# comms_v2.net
KiCad netlist of a schematic drawn in EAGLE
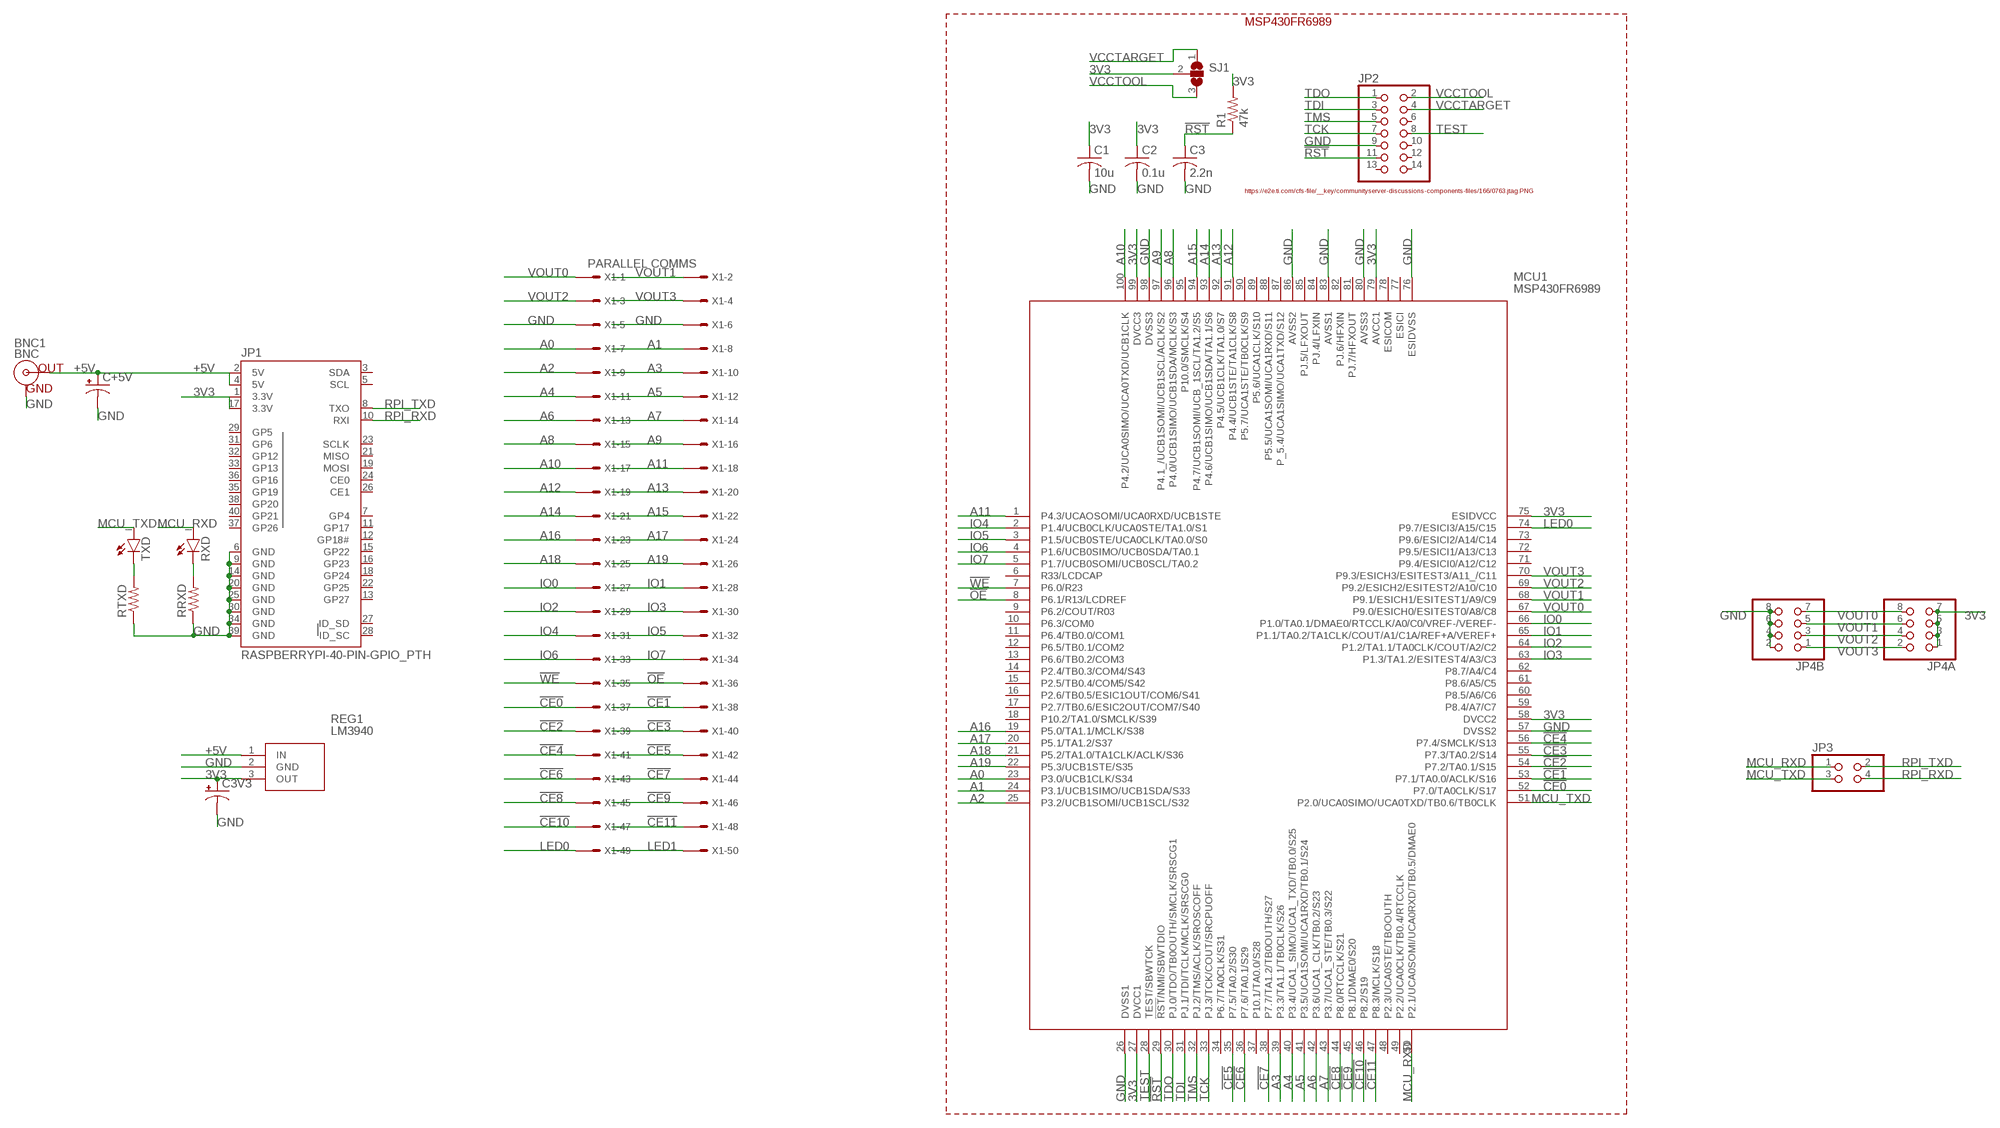
[diagram p0: schematic, sheet 1]

(export (version "E")
  (design (tool "Eeschema 10.0.6"))
  (components
    (comp (ref "BNC1")
      (value "BNC")
      (footprint "eagle-import:BNC")
      (libsource (lib "eagle-import") (part "BNCPTH"))
    )
    (comp (ref "C+5V")
      (value "CPOL-USE2.5-6")
      (footprint "eagle-import:E2,5-6")
      (libsource (lib "eagle-import") (part "CPOL-USE2.5-6"))
    )
    (comp (ref "C1")
      (value "10u")
      (footprint "eagle-import:C0805")
      (libsource (lib "eagle-import") (part "C-USC0805"))
    )
    (comp (ref "C2")
      (value "0.1u")
      (footprint "eagle-import:C0805")
      (libsource (lib "eagle-import") (part "C-USC0805"))
    )
    (comp (ref "C3")
      (value "2.2n")
      (footprint "eagle-import:C0805")
      (libsource (lib "eagle-import") (part "C-USC0805"))
    )
    (comp (ref "C3V3")
      (value "CPOL-USE2.5-6")
      (footprint "eagle-import:E2,5-6")
      (libsource (lib "eagle-import") (part "CPOL-USE2.5-6"))
    )
    (comp (ref "JP1")
      (value "RASPBERRYPI-40-PIN-GPIO_PTH")
      (footprint "eagle-import:2X20_SHROUDED")
      (libsource (lib "eagle-import") (part "RASPBERRYPI-40-PIN-GPIO_PTH"))
    )
    (comp (ref "JP2")
      (value "PINHD-2X7")
      (footprint "eagle-import:2X07")
      (libsource (lib "eagle-import") (part "PINHD-2X7"))
    )
    (comp (ref "JP3")
      (value "PINHD-2X2")
      (footprint "eagle-import:2X02")
      (libsource (lib "eagle-import") (part "PINHD-2X2"))
    )
    (comp (ref "JP4A")
      (value "PINHD-2X4")
      (footprint "eagle-import:2X04")
      (libsource (lib "eagle-import") (part "PINHD-2X4"))
    )
    (comp (ref "JP4B")
      (value "PINHD-2X4")
      (footprint "eagle-import:2X04")
      (libsource (lib "eagle-import") (part "PINHD-2X4"))
    )
    (comp (ref "MCU1")
      (value "MSP430FR6989")
      (footprint "eagle-import:QFP50P1600X1600X160-100N")
      (fields
        (field (name "ARROW_PART_NUMBER") "MSP430FR6989IPZR")
        (field (name "MOUSER_PART_NUMBER") "595-MSP430FR6989IPZR")
      )
      (libsource (lib "eagle-import") (part "MSP430FR6989IPZR"))
    )
    (comp (ref "R1")
      (value "47k")
      (footprint "eagle-import:R0805")
      (libsource (lib "eagle-import") (part "R-US_R0805"))
    )
    (comp (ref "REG1")
      (value "LM3940")
      (footprint "eagle-import:TO254P470X1028X1955-3P")
      (fields
        (field (name "ARROW_PART_NUMBER") "LM3940IT-3.3/NOPB")
        (field (name "MOUSER_PART_NUMBER") "926-LM3940IT-3.3NOPB")
      )
      (libsource (lib "eagle-import") (part "LM3940IT-3.3_NOPB"))
    )
    (comp (ref "RRXD")
      (value "R-US_0204/7")
      (footprint "eagle-import:0204_7")
      (libsource (lib "eagle-import") (part "R-US_0204/7"))
    )
    (comp (ref "RTXD")
      (value "R-US_0204/7")
      (footprint "eagle-import:0204_7")
      (libsource (lib "eagle-import") (part "R-US_0204/7"))
    )
    (comp (ref "RXD")
      (value "LED3MM")
      (footprint "eagle-import:LED3MM")
      (libsource (lib "eagle-import") (part "LED3MM"))
    )
    (comp (ref "SJ1")
      (value "SJ2W")
      (footprint "eagle-import:SJ_2")
      (libsource (lib "eagle-import") (part "SJ2W"))
    )
    (comp (ref "TXD")
      (value "LED3MM")
      (footprint "eagle-import:LED3MM")
      (libsource (lib "eagle-import") (part "LED3MM"))
    )
    (comp (ref "X1")
      (value "PARALLEL COMMS")
      (footprint "eagle-import:057-050-1")
      (libsource (lib "eagle-import") (part "057-050-1"))
    )
  )
  (nets
    (net (code "1") (name "/+5V") (class "Default")
      (node (ref "BNC1") (pin "S") (pinfunction "OUT_S") (pintype "bidirectional"))
      (node (ref "C+5V") (pin "+") (pinfunction "+_+") (pintype "passive"))
      (node (ref "JP1") (pin "2") (pinfunction "5V_2") (pintype "power_in"))
      (node (ref "JP1") (pin "4") (pinfunction "5V_4") (pintype "power_in"))
      (node (ref "REG1") (pin "1") (pinfunction "IN_1") (pintype "bidirectional"))
    )
    (net (code "2") (name "/3V3") (class "Default")
      (node (ref "C1") (pin "1") (pinfunction "1_1") (pintype "passive"))
      (node (ref "C2") (pin "1") (pinfunction "1_1") (pintype "passive"))
      (node (ref "C3V3") (pin "+") (pinfunction "+_+") (pintype "passive"))
      (node (ref "JP1") (pin "1") (pinfunction "3.3V_1") (pintype "power_in"))
      (node (ref "JP1") (pin "17") (pinfunction "3.3V_17") (pintype "power_in"))
      (node (ref "JP4A") (pin "1") (pinfunction "1_1") (pintype "passive"))
      (node (ref "JP4A") (pin "3") (pinfunction "3_3") (pintype "passive"))
      (node (ref "JP4A") (pin "5") (pinfunction "5_5") (pintype "passive"))
      (node (ref "JP4A") (pin "7") (pinfunction "7_7") (pintype "passive"))
      (node (ref "MCU1") (pin "27") (pinfunction "DVCC1_27") (pintype "bidirectional"))
      (node (ref "MCU1") (pin "58") (pinfunction "DVCC2_58") (pintype "bidirectional"))
      (node (ref "MCU1") (pin "75") (pinfunction "ESIDVCC_75") (pintype "bidirectional"))
      (node (ref "MCU1") (pin "79") (pinfunction "AVCC1_79") (pintype "bidirectional"))
      (node (ref "MCU1") (pin "99") (pinfunction "DVCC3_99") (pintype "bidirectional"))
      (node (ref "R1") (pin "2") (pinfunction "2_2") (pintype "passive"))
      (node (ref "REG1") (pin "3") (pinfunction "OUT_3") (pintype "bidirectional"))
      (node (ref "SJ1") (pin "2") (pinfunction "2_2") (pintype "passive"))
    )
    (net (code "3") (name "/A0") (class "Default")
      (node (ref "MCU1") (pin "23") (pinfunction "P3.0/UCB1CLK/S34_23") (pintype "bidirectional"))
      (node (ref "X1") (pin "7") (pinfunction "S_7") (pintype "passive"))
    )
    (net (code "4") (name "/A1") (class "Default")
      (node (ref "MCU1") (pin "24") (pinfunction "P3.1/UCB1SIMO/UCB1SDA/S33_24") (pintype "bidirectional"))
      (node (ref "X1") (pin "8") (pinfunction "S_8") (pintype "passive"))
    )
    (net (code "5") (name "/A2") (class "Default")
      (node (ref "MCU1") (pin "25") (pinfunction "P3.2/UCB1SOMI/UCB1SCL/S32_25") (pintype "bidirectional"))
      (node (ref "X1") (pin "9") (pinfunction "S_9") (pintype "passive"))
    )
    (net (code "6") (name "/A3") (class "Default")
      (node (ref "MCU1") (pin "39") (pinfunction "P3.3/TA1.1/TB0CLK/S26_39") (pintype "bidirectional"))
      (node (ref "X1") (pin "10") (pinfunction "S_10") (pintype "passive"))
    )
    (net (code "7") (name "/A4") (class "Default")
      (node (ref "MCU1") (pin "40") (pinfunction "P3.4/UCA1_SIMO/UCA1_TXD/TB0.0/S25_40") (pintype "bidirectional"))
      (node (ref "X1") (pin "11") (pinfunction "S_11") (pintype "passive"))
    )
    (net (code "8") (name "/A5") (class "Default")
      (node (ref "MCU1") (pin "41") (pinfunction "P3.5/UCA1SOMI/UCA1RXD/TB0.1/S24_41") (pintype "bidirectional"))
      (node (ref "X1") (pin "12") (pinfunction "S_12") (pintype "passive"))
    )
    (net (code "9") (name "/A6") (class "Default")
      (node (ref "MCU1") (pin "42") (pinfunction "P3.6/UCA1_CLK/TB0.2/S23_42") (pintype "bidirectional"))
      (node (ref "X1") (pin "13") (pinfunction "S_13") (pintype "passive"))
    )
    (net (code "10") (name "/A7") (class "Default")
      (node (ref "MCU1") (pin "43") (pinfunction "P3.7/UCA1_STE/TB0.3/S22_43") (pintype "bidirectional"))
      (node (ref "X1") (pin "14") (pinfunction "S_14") (pintype "passive"))
    )
    (net (code "11") (name "/A8") (class "Default")
      (node (ref "MCU1") (pin "96") (pinfunction "P4.0/UCB1SIMO/UCB1SDA/MCLK/S3_96") (pintype "bidirectional"))
      (node (ref "X1") (pin "15") (pinfunction "S_15") (pintype "passive"))
    )
    (net (code "12") (name "/A9") (class "Default")
      (node (ref "MCU1") (pin "97") (pinfunction "P4.1_/UCB1SOMI/UCB1SCL/ACLK/S2_97") (pintype "bidirectional"))
      (node (ref "X1") (pin "16") (pinfunction "S_16") (pintype "passive"))
    )
    (net (code "13") (name "/A10") (class "Default")
      (node (ref "MCU1") (pin "100") (pinfunction "P4.2/UCA0SIMO/UCA0TXD/UCB1CLK_100") (pintype "bidirectional"))
      (node (ref "X1") (pin "17") (pinfunction "S_17") (pintype "passive"))
    )
    (net (code "14") (name "/A11") (class "Default")
      (node (ref "MCU1") (pin "1") (pinfunction "P4.3/UCAOSOMI/UCA0RXD/UCB1STE_1") (pintype "bidirectional"))
      (node (ref "X1") (pin "18") (pinfunction "S_18") (pintype "passive"))
    )
    (net (code "15") (name "/A12") (class "Default")
      (node (ref "MCU1") (pin "91") (pinfunction "P4.4/UCB1STE/TA1CLK/S8_91") (pintype "bidirectional"))
      (node (ref "X1") (pin "19") (pinfunction "S_19") (pintype "passive"))
    )
    (net (code "16") (name "/A13") (class "Default")
      (node (ref "MCU1") (pin "92") (pinfunction "P4.5/UCB1CLK/TA1.0/S7_92") (pintype "bidirectional"))
      (node (ref "X1") (pin "20") (pinfunction "S_20") (pintype "passive"))
    )
    (net (code "17") (name "/A14") (class "Default")
      (node (ref "MCU1") (pin "93") (pinfunction "P4.6/UCB1SIMO/UCB1SDA/TA1.1/S6_93") (pintype "bidirectional"))
      (node (ref "X1") (pin "21") (pinfunction "S_21") (pintype "passive"))
    )
    (net (code "18") (name "/A15") (class "Default")
      (node (ref "MCU1") (pin "94") (pinfunction "P4.7/UCB1SOMI/UCB_1SCL/TA1.2/S5_94") (pintype "bidirectional"))
      (node (ref "X1") (pin "22") (pinfunction "S_22") (pintype "passive"))
    )
    (net (code "19") (name "/A16") (class "Default")
      (node (ref "MCU1") (pin "19") (pinfunction "P5.0/TA1.1/MCLK/S38_19") (pintype "bidirectional"))
      (node (ref "X1") (pin "23") (pinfunction "S_23") (pintype "passive"))
    )
    (net (code "20") (name "/A17") (class "Default")
      (node (ref "MCU1") (pin "20") (pinfunction "P5.1/TA1.2/S37_20") (pintype "bidirectional"))
      (node (ref "X1") (pin "24") (pinfunction "S_24") (pintype "passive"))
    )
    (net (code "21") (name "/A18") (class "Default")
      (node (ref "MCU1") (pin "21") (pinfunction "P5.2/TA1.0/TA1CLK/ACLK/S36_21") (pintype "bidirectional"))
      (node (ref "X1") (pin "25") (pinfunction "S_25") (pintype "passive"))
    )
    (net (code "22") (name "/A19") (class "Default")
      (node (ref "MCU1") (pin "22") (pinfunction "P5.3/UCB1STE/S35_22") (pintype "bidirectional"))
      (node (ref "X1") (pin "26") (pinfunction "S_26") (pintype "passive"))
    )
    (net (code "23") (name "/GND") (class "Default")
      (node (ref "BNC1") (pin "GND") (pinfunction "GND_GND") (pintype "bidirectional"))
      (node (ref "C+5V") (pin "-") (pinfunction "-_-") (pintype "passive"))
      (node (ref "C1") (pin "2") (pinfunction "2_2") (pintype "passive"))
      (node (ref "C2") (pin "2") (pinfunction "2_2") (pintype "passive"))
      (node (ref "C3") (pin "2") (pinfunction "2_2") (pintype "passive"))
      (node (ref "C3V3") (pin "-") (pinfunction "-_-") (pintype "passive"))
      (node (ref "JP1") (pin "14") (pinfunction "GND_14") (pintype "power_in"))
      (node (ref "JP1") (pin "20") (pinfunction "GND_20") (pintype "power_in"))
      (node (ref "JP1") (pin "25") (pinfunction "GND_25") (pintype "power_in"))
      (node (ref "JP1") (pin "30") (pinfunction "GND_30") (pintype "power_in"))
      (node (ref "JP1") (pin "34") (pinfunction "GND_34") (pintype "power_in"))
      (node (ref "JP1") (pin "39") (pinfunction "GND_39") (pintype "power_in"))
      (node (ref "JP1") (pin "6") (pinfunction "GND_6") (pintype "power_in"))
      (node (ref "JP1") (pin "9") (pinfunction "GND_9") (pintype "power_in"))
      (node (ref "JP2") (pin "9") (pinfunction "9_9") (pintype "passive"))
      (node (ref "JP4B") (pin "2") (pinfunction "2_2") (pintype "passive"))
      (node (ref "JP4B") (pin "4") (pinfunction "4_4") (pintype "passive"))
      (node (ref "JP4B") (pin "6") (pinfunction "6_6") (pintype "passive"))
      (node (ref "JP4B") (pin "8") (pinfunction "8_8") (pintype "passive"))
      (node (ref "MCU1") (pin "26") (pinfunction "DVSS1_26") (pintype "bidirectional"))
      (node (ref "MCU1") (pin "57") (pinfunction "DVSS2_57") (pintype "bidirectional"))
      (node (ref "MCU1") (pin "76") (pinfunction "ESIDVSS_76") (pintype "bidirectional"))
      (node (ref "MCU1") (pin "80") (pinfunction "AVSS3_80") (pintype "bidirectional"))
      (node (ref "MCU1") (pin "83") (pinfunction "AVSS1_83") (pintype "bidirectional"))
      (node (ref "MCU1") (pin "86") (pinfunction "AVSS2_86") (pintype "bidirectional"))
      (node (ref "MCU1") (pin "98") (pinfunction "DVSS3_98") (pintype "bidirectional"))
      (node (ref "REG1") (pin "2") (pinfunction "GND_2") (pintype "bidirectional"))
      (node (ref "RRXD") (pin "1") (pinfunction "1_1") (pintype "passive"))
      (node (ref "RTXD") (pin "1") (pinfunction "1_1") (pintype "passive"))
      (node (ref "X1") (pin "5") (pinfunction "S_5") (pintype "passive"))
      (node (ref "X1") (pin "6") (pinfunction "S_6") (pintype "passive"))
    )
    (net (code "24") (name "/IO0") (class "Default")
      (node (ref "MCU1") (pin "66") (pinfunction "P1.0/TA0.1/DMAE0/RTCCLK/A0/C0/VREF-/VEREF-_66") (pintype "bidirectional"))
      (node (ref "X1") (pin "27") (pinfunction "S_27") (pintype "passive"))
    )
    (net (code "25") (name "/IO1") (class "Default")
      (node (ref "MCU1") (pin "65") (pinfunction "P1.1/TA0.2/TA1CLK/COUT/A1/C1A/REF+A/VEREF+_65") (pintype "bidirectional"))
      (node (ref "X1") (pin "28") (pinfunction "S_28") (pintype "passive"))
    )
    (net (code "26") (name "/IO2") (class "Default")
      (node (ref "MCU1") (pin "64") (pinfunction "P1.2/TA1.1/TA0CLK/COUT/A2/C2_64") (pintype "bidirectional"))
      (node (ref "X1") (pin "29") (pinfunction "S_29") (pintype "passive"))
    )
    (net (code "27") (name "/IO3") (class "Default")
      (node (ref "MCU1") (pin "63") (pinfunction "P1.3/TA1.2/ESITEST4/A3/C3_63") (pintype "bidirectional"))
      (node (ref "X1") (pin "30") (pinfunction "S_30") (pintype "passive"))
    )
    (net (code "28") (name "/IO4") (class "Default")
      (node (ref "MCU1") (pin "2") (pinfunction "P1.4/UCB0CLK/UCA0STE/TA1.0/S1_2") (pintype "bidirectional"))
      (node (ref "X1") (pin "31") (pinfunction "S_31") (pintype "passive"))
    )
    (net (code "29") (name "/IO5") (class "Default")
      (node (ref "MCU1") (pin "3") (pinfunction "P1.5/UCB0STE/UCA0CLK/TA0.0/S0_3") (pintype "bidirectional"))
      (node (ref "X1") (pin "32") (pinfunction "S_32") (pintype "passive"))
    )
    (net (code "30") (name "/IO6") (class "Default")
      (node (ref "MCU1") (pin "4") (pinfunction "P1.6/UCB0SIMO/UCB0SDA/TA0.1_4") (pintype "bidirectional"))
      (node (ref "X1") (pin "33") (pinfunction "S_33") (pintype "passive"))
    )
    (net (code "31") (name "/IO7") (class "Default")
      (node (ref "MCU1") (pin "5") (pinfunction "P1.7/UCB0SOMI/UCB0SCL/TA0.2_5") (pintype "bidirectional"))
      (node (ref "X1") (pin "34") (pinfunction "S_34") (pintype "passive"))
    )
    (net (code "32") (name "/LED0") (class "Default")
      (node (ref "MCU1") (pin "74") (pinfunction "P9.7/ESICI3/A15/C15_74") (pintype "bidirectional"))
      (node (ref "X1") (pin "49") (pinfunction "S_49") (pintype "passive"))
    )
    (net (code "33") (name "/LED1") (class "Default")
      (node (ref "X1") (pin "50") (pinfunction "S_50") (pintype "passive"))
    )
    (net (code "34") (name "/MCU_RXD") (class "Default")
      (node (ref "JP3") (pin "1") (pinfunction "1_1") (pintype "passive"))
      (node (ref "MCU1") (pin "50") (pinfunction "P2.1/UCA0SOMI/UCA0RXD/TB0.5/DMAE0_50") (pintype "bidirectional"))
      (node (ref "RXD") (pin "A") (pinfunction "A_A") (pintype "passive"))
    )
    (net (code "35") (name "/MCU_TXD") (class "Default")
      (node (ref "JP3") (pin "3") (pinfunction "3_3") (pintype "passive"))
      (node (ref "MCU1") (pin "51") (pinfunction "P2.0/UCA0SIMO/UCA0TXD/TB0.6/TB0CLK_51") (pintype "bidirectional"))
      (node (ref "TXD") (pin "A") (pinfunction "A_A") (pintype "passive"))
    )
    (net (code "36") (name "/RPI_RXD") (class "Default")
      (node (ref "JP1") (pin "10") (pinfunction "RXI_10") (pintype "input"))
      (node (ref "JP3") (pin "4") (pinfunction "4_4") (pintype "passive"))
    )
    (net (code "37") (name "/RPI_TXD") (class "Default")
      (node (ref "JP1") (pin "8") (pinfunction "TXO_8") (pintype "output"))
      (node (ref "JP3") (pin "2") (pinfunction "2_2") (pintype "passive"))
    )
    (net (code "38") (name "/TCK") (class "Default")
      (node (ref "JP2") (pin "7") (pinfunction "7_7") (pintype "passive"))
      (node (ref "MCU1") (pin "33") (pinfunction "PJ.3/TCK/COUT/SRCPUOFF_33") (pintype "bidirectional"))
    )
    (net (code "39") (name "/TDI") (class "Default")
      (node (ref "JP2") (pin "3") (pinfunction "3_3") (pintype "passive"))
      (node (ref "MCU1") (pin "31") (pinfunction "PJ.1/TDI/TCLK/MCLK/SRSCG0_31") (pintype "bidirectional"))
    )
    (net (code "40") (name "/TDO") (class "Default")
      (node (ref "JP2") (pin "1") (pinfunction "1_1") (pintype "passive"))
      (node (ref "MCU1") (pin "30") (pinfunction "PJ.0/TDO/TB0OUTH/SMCLK/SRSCG1_30") (pintype "bidirectional"))
    )
    (net (code "41") (name "/TEST") (class "Default")
      (node (ref "JP2") (pin "8") (pinfunction "8_8") (pintype "passive"))
      (node (ref "MCU1") (pin "28") (pinfunction "TEST/SBWTCK_28") (pintype "bidirectional"))
    )
    (net (code "42") (name "/TMS") (class "Default")
      (node (ref "JP2") (pin "5") (pinfunction "5_5") (pintype "passive"))
      (node (ref "MCU1") (pin "32") (pinfunction "PJ.2/TMS/ACLK/SROSCOFF_32") (pintype "bidirectional"))
    )
    (net (code "43") (name "/VCCTARGET") (class "Default")
      (node (ref "JP2") (pin "4") (pinfunction "4_4") (pintype "passive"))
      (node (ref "SJ1") (pin "1") (pinfunction "1_1") (pintype "passive"))
    )
    (net (code "44") (name "/VCCTOOL") (class "Default")
      (node (ref "JP2") (pin "2") (pinfunction "2_2") (pintype "passive"))
      (node (ref "SJ1") (pin "3") (pinfunction "3_3") (pintype "passive"))
    )
    (net (code "45") (name "/VOUT0") (class "Default")
      (node (ref "JP4A") (pin "8") (pinfunction "8_8") (pintype "passive"))
      (node (ref "JP4B") (pin "7") (pinfunction "7_7") (pintype "passive"))
      (node (ref "MCU1") (pin "67") (pinfunction "P9.0/ESICH0/ESITEST0/A8/C8_67") (pintype "bidirectional"))
      (node (ref "X1") (pin "1") (pinfunction "S_1") (pintype "passive"))
    )
    (net (code "46") (name "/VOUT1") (class "Default")
      (node (ref "JP4A") (pin "6") (pinfunction "6_6") (pintype "passive"))
      (node (ref "JP4B") (pin "5") (pinfunction "5_5") (pintype "passive"))
      (node (ref "MCU1") (pin "68") (pinfunction "P9.1/ESICH1/ESITEST1/A9/C9_68") (pintype "bidirectional"))
      (node (ref "X1") (pin "2") (pinfunction "S_2") (pintype "passive"))
    )
    (net (code "47") (name "/VOUT2") (class "Default")
      (node (ref "JP4A") (pin "4") (pinfunction "4_4") (pintype "passive"))
      (node (ref "JP4B") (pin "3") (pinfunction "3_3") (pintype "passive"))
      (node (ref "MCU1") (pin "69") (pinfunction "P9.2/ESICH2/ESITEST2/A10/C10_69") (pintype "bidirectional"))
      (node (ref "X1") (pin "3") (pinfunction "S_3") (pintype "passive"))
    )
    (net (code "48") (name "/VOUT3") (class "Default")
      (node (ref "JP4A") (pin "2") (pinfunction "2_2") (pintype "passive"))
      (node (ref "JP4B") (pin "1") (pinfunction "1_1") (pintype "passive"))
      (node (ref "MCU1") (pin "70") (pinfunction "P9.3/ESICH3/ESITEST3/A11_/C11_70") (pintype "bidirectional"))
      (node (ref "X1") (pin "4") (pinfunction "S_4") (pintype "passive"))
    )
    (net (code "49") (name "/~{CE0}") (class "Default")
      (node (ref "MCU1") (pin "52") (pinfunction "P7.0/TA0CLK/S17_52") (pintype "bidirectional"))
      (node (ref "X1") (pin "37") (pinfunction "S_37") (pintype "passive"))
    )
    (net (code "50") (name "/~{CE1}") (class "Default")
      (node (ref "MCU1") (pin "53") (pinfunction "P7.1/TA0.0/ACLK/S16_53") (pintype "bidirectional"))
      (node (ref "X1") (pin "38") (pinfunction "S_38") (pintype "passive"))
    )
    (net (code "51") (name "/~{CE2}") (class "Default")
      (node (ref "MCU1") (pin "54") (pinfunction "P7.2/TA0.1/S15_54") (pintype "bidirectional"))
      (node (ref "X1") (pin "39") (pinfunction "S_39") (pintype "passive"))
    )
    (net (code "52") (name "/~{CE3}") (class "Default")
      (node (ref "MCU1") (pin "55") (pinfunction "P7.3/TA0.2/S14_55") (pintype "bidirectional"))
      (node (ref "X1") (pin "40") (pinfunction "S_40") (pintype "passive"))
    )
    (net (code "53") (name "/~{CE4}") (class "Default")
      (node (ref "MCU1") (pin "56") (pinfunction "P7.4/SMCLK/S13_56") (pintype "bidirectional"))
      (node (ref "X1") (pin "41") (pinfunction "S_41") (pintype "passive"))
    )
    (net (code "54") (name "/~{CE5}") (class "Default")
      (node (ref "MCU1") (pin "35") (pinfunction "P7.5/TA0.2/S30_35") (pintype "bidirectional"))
      (node (ref "X1") (pin "42") (pinfunction "S_42") (pintype "passive"))
    )
    (net (code "55") (name "/~{CE6}") (class "Default")
      (node (ref "MCU1") (pin "36") (pinfunction "P7.6/TA0.1/S29_36") (pintype "bidirectional"))
      (node (ref "X1") (pin "43") (pinfunction "S_43") (pintype "passive"))
    )
    (net (code "56") (name "/~{CE7}") (class "Default")
      (node (ref "MCU1") (pin "38") (pinfunction "P7.7/TA1.2/TB0OUTH/S27_38") (pintype "bidirectional"))
      (node (ref "X1") (pin "44") (pinfunction "S_44") (pintype "passive"))
    )
    (net (code "57") (name "/~{CE8}") (class "Default")
      (node (ref "MCU1") (pin "44") (pinfunction "P8.0/RTCCLK/S21_44") (pintype "bidirectional"))
      (node (ref "X1") (pin "45") (pinfunction "S_45") (pintype "passive"))
    )
    (net (code "58") (name "/~{CE9}") (class "Default")
      (node (ref "MCU1") (pin "45") (pinfunction "P8.1/DMAE0/S20_45") (pintype "bidirectional"))
      (node (ref "X1") (pin "46") (pinfunction "S_46") (pintype "passive"))
    )
    (net (code "59") (name "/~{CE10}") (class "Default")
      (node (ref "MCU1") (pin "46") (pinfunction "P8.2/S19_46") (pintype "bidirectional"))
      (node (ref "X1") (pin "47") (pinfunction "S_47") (pintype "passive"))
    )
    (net (code "60") (name "/~{CE11}") (class "Default")
      (node (ref "MCU1") (pin "47") (pinfunction "P8.3/MCLK/S18_47") (pintype "bidirectional"))
      (node (ref "X1") (pin "48") (pinfunction "S_48") (pintype "passive"))
    )
    (net (code "61") (name "/~{OE}") (class "Default")
      (node (ref "MCU1") (pin "8") (pinfunction "P6.1/R13/LCDREF_8") (pintype "bidirectional"))
      (node (ref "X1") (pin "36") (pinfunction "S_36") (pintype "passive"))
    )
    (net (code "62") (name "/~{RST}") (class "Default")
      (node (ref "C3") (pin "1") (pinfunction "1_1") (pintype "passive"))
      (node (ref "JP2") (pin "11") (pinfunction "11_11") (pintype "passive"))
      (node (ref "MCU1") (pin "29") (pinfunction "~{RST}/NMI/SBWTDIO_29") (pintype "bidirectional"))
      (node (ref "R1") (pin "1") (pinfunction "1_1") (pintype "passive"))
    )
    (net (code "63") (name "/~{WE}") (class "Default")
      (node (ref "MCU1") (pin "7") (pinfunction "P6.0/R23_7") (pintype "bidirectional"))
      (node (ref "X1") (pin "35") (pinfunction "S_35") (pintype "passive"))
    )
    (net (code "64") (name "Net-(RXD-C)") (class "Default")
      (node (ref "RRXD") (pin "2") (pinfunction "2_2") (pintype "passive"))
      (node (ref "RXD") (pin "K") (pinfunction "C_K") (pintype "passive"))
    )
    (net (code "65") (name "Net-(TXD-C)") (class "Default")
      (node (ref "RTXD") (pin "2") (pinfunction "2_2") (pintype "passive"))
      (node (ref "TXD") (pin "K") (pinfunction "C_K") (pintype "passive"))
    )
    (net (code "66") (name "unconnected-(JP1-CE0-Pad24)") (class "Default")
      (node (ref "JP1") (pin "24") (pinfunction "CE0_24") (pintype "output"))
    )
    (net (code "67") (name "unconnected-(JP1-CE1-Pad26)") (class "Default")
      (node (ref "JP1") (pin "26") (pinfunction "CE1_26") (pintype "output"))
    )
    (net (code "68") (name "unconnected-(JP1-GP4-Pad7)") (class "Default")
      (node (ref "JP1") (pin "7") (pinfunction "GP4_7") (pintype "bidirectional"))
    )
    (net (code "69") (name "unconnected-(JP1-GP5-Pad29)") (class "Default")
      (node (ref "JP1") (pin "29") (pinfunction "GP5_29") (pintype "bidirectional"))
    )
    (net (code "70") (name "unconnected-(JP1-GP6-Pad31)") (class "Default")
      (node (ref "JP1") (pin "31") (pinfunction "GP6_31") (pintype "bidirectional"))
    )
    (net (code "71") (name "unconnected-(JP1-GP12-Pad32)") (class "Default")
      (node (ref "JP1") (pin "32") (pinfunction "GP12_32") (pintype "bidirectional"))
    )
    (net (code "72") (name "unconnected-(JP1-GP13-Pad33)") (class "Default")
      (node (ref "JP1") (pin "33") (pinfunction "GP13_33") (pintype "bidirectional"))
    )
    (net (code "73") (name "unconnected-(JP1-GP16-Pad36)") (class "Default")
      (node (ref "JP1") (pin "36") (pinfunction "GP16_36") (pintype "bidirectional"))
    )
    (net (code "74") (name "unconnected-(JP1-GP17-Pad11)") (class "Default")
      (node (ref "JP1") (pin "11") (pinfunction "GP17_11") (pintype "bidirectional"))
    )
    (net (code "75") (name "unconnected-(JP1-GP18#-Pad12)") (class "Default")
      (node (ref "JP1") (pin "12") (pinfunction "GP18#_12") (pintype "bidirectional"))
    )
    (net (code "76") (name "unconnected-(JP1-GP19-Pad35)") (class "Default")
      (node (ref "JP1") (pin "35") (pinfunction "GP19_35") (pintype "bidirectional"))
    )
    (net (code "77") (name "unconnected-(JP1-GP20-Pad38)") (class "Default")
      (node (ref "JP1") (pin "38") (pinfunction "GP20_38") (pintype "bidirectional"))
    )
    (net (code "78") (name "unconnected-(JP1-GP21-Pad40)") (class "Default")
      (node (ref "JP1") (pin "40") (pinfunction "GP21_40") (pintype "bidirectional"))
    )
    (net (code "79") (name "unconnected-(JP1-GP22-Pad15)") (class "Default")
      (node (ref "JP1") (pin "15") (pinfunction "GP22_15") (pintype "bidirectional"))
    )
    (net (code "80") (name "unconnected-(JP1-GP23-Pad16)") (class "Default")
      (node (ref "JP1") (pin "16") (pinfunction "GP23_16") (pintype "bidirectional"))
    )
    (net (code "81") (name "unconnected-(JP1-GP24-Pad18)") (class "Default")
      (node (ref "JP1") (pin "18") (pinfunction "GP24_18") (pintype "bidirectional"))
    )
    (net (code "82") (name "unconnected-(JP1-GP25-Pad22)") (class "Default")
      (node (ref "JP1") (pin "22") (pinfunction "GP25_22") (pintype "bidirectional"))
    )
    (net (code "83") (name "unconnected-(JP1-GP26-Pad37)") (class "Default")
      (node (ref "JP1") (pin "37") (pinfunction "GP26_37") (pintype "bidirectional"))
    )
    (net (code "84") (name "unconnected-(JP1-GP27-Pad13)") (class "Default")
      (node (ref "JP1") (pin "13") (pinfunction "GP27_13") (pintype "bidirectional"))
    )
    (net (code "85") (name "unconnected-(JP1-ID_SC-Pad28)") (class "Default")
      (node (ref "JP1") (pin "28") (pinfunction "ID_SC_28") (pintype "bidirectional"))
    )
    (net (code "86") (name "unconnected-(JP1-ID_SD-Pad27)") (class "Default")
      (node (ref "JP1") (pin "27") (pinfunction "ID_SD_27") (pintype "bidirectional"))
    )
    (net (code "87") (name "unconnected-(JP1-MISO-Pad21)") (class "Default")
      (node (ref "JP1") (pin "21") (pinfunction "MISO_21") (pintype "input"))
    )
    (net (code "88") (name "unconnected-(JP1-MOSI-Pad19)") (class "Default")
      (node (ref "JP1") (pin "19") (pinfunction "MOSI_19") (pintype "output"))
    )
    (net (code "89") (name "unconnected-(JP1-SCL-Pad5)") (class "Default")
      (node (ref "JP1") (pin "5") (pinfunction "SCL_5") (pintype "bidirectional"))
    )
    (net (code "90") (name "unconnected-(JP1-SCLK-Pad23)") (class "Default")
      (node (ref "JP1") (pin "23") (pinfunction "SCLK_23") (pintype "output"))
    )
    (net (code "91") (name "unconnected-(JP1-SDA-Pad3)") (class "Default")
      (node (ref "JP1") (pin "3") (pinfunction "SDA_3") (pintype "bidirectional"))
    )
    (net (code "92") (name "unconnected-(JP2-Pad6)") (class "Default")
      (node (ref "JP2") (pin "6") (pinfunction "6_6") (pintype "passive"))
    )
    (net (code "93") (name "unconnected-(JP2-Pad10)") (class "Default")
      (node (ref "JP2") (pin "10") (pinfunction "10_10") (pintype "passive"))
    )
    (net (code "94") (name "unconnected-(JP2-Pad12)") (class "Default")
      (node (ref "JP2") (pin "12") (pinfunction "12_12") (pintype "passive"))
    )
    (net (code "95") (name "unconnected-(JP2-Pad13)") (class "Default")
      (node (ref "JP2") (pin "13") (pinfunction "13_13") (pintype "passive"))
    )
    (net (code "96") (name "unconnected-(JP2-Pad14)") (class "Default")
      (node (ref "JP2") (pin "14") (pinfunction "14_14") (pintype "passive"))
    )
    (net (code "97") (name "unconnected-(MCU1-ESICI-Pad77)") (class "Default")
      (node (ref "MCU1") (pin "77") (pinfunction "ESICI_77") (pintype "bidirectional"))
    )
    (net (code "98") (name "unconnected-(MCU1-ESICOM-Pad78)") (class "Default")
      (node (ref "MCU1") (pin "78") (pinfunction "ESICOM_78") (pintype "bidirectional"))
    )
    (net (code "99") (name "unconnected-(MCU1-P2.2{slash}UCA0CLK{slash}TB0.4{slash}RTCCLK-Pad49)") (class "Default")
      (node (ref "MCU1") (pin "49") (pinfunction "P2.2/UCA0CLK/TB0.4/RTCCLK_49") (pintype "bidirectional"))
    )
    (net (code "100") (name "unconnected-(MCU1-P2.3{slash}UCA0STE{slash}TBOOUTH-Pad48)") (class "Default")
      (node (ref "MCU1") (pin "48") (pinfunction "P2.3/UCA0STE/TBOOUTH_48") (pintype "bidirectional"))
    )
    (net (code "101") (name "unconnected-(MCU1-P2.4{slash}TB0.3{slash}COM4{slash}S43-Pad14)") (class "Default")
      (node (ref "MCU1") (pin "14") (pinfunction "P2.4/TB0.3/COM4/S43_14") (pintype "bidirectional"))
    )
    (net (code "102") (name "unconnected-(MCU1-P2.5{slash}TB0.4{slash}COM5{slash}S42-Pad15)") (class "Default")
      (node (ref "MCU1") (pin "15") (pinfunction "P2.5/TB0.4/COM5/S42_15") (pintype "bidirectional"))
    )
    (net (code "103") (name "unconnected-(MCU1-P2.6{slash}TB0.5{slash}ESIC1OUT{slash}COM6{slash}S41-Pad16)") (class "Default")
      (node (ref "MCU1") (pin "16") (pinfunction "P2.6/TB0.5/ESIC1OUT/COM6/S41_16") (pintype "bidirectional"))
    )
    (net (code "104") (name "unconnected-(MCU1-P2.7{slash}TB0.6{slash}ESIC2OUT{slash}COM7{slash}S40-Pad17)") (class "Default")
      (node (ref "MCU1") (pin "17") (pinfunction "P2.7/TB0.6/ESIC2OUT/COM7/S40_17") (pintype "bidirectional"))
    )
    (net (code "105") (name "unconnected-(MCU1-P5.5{slash}UCA1SOMI{slash}UCA1RXD{slash}S11-Pad88)") (class "Default")
      (node (ref "MCU1") (pin "88") (pinfunction "P5.5/UCA1SOMI/UCA1RXD/S11_88") (pintype "bidirectional"))
    )
    (net (code "106") (name "unconnected-(MCU1-P5.6{slash}UCA1CLK{slash}S10-Pad89)") (class "Default")
      (node (ref "MCU1") (pin "89") (pinfunction "P5.6/UCA1CLK/S10_89") (pintype "bidirectional"))
    )
    (net (code "107") (name "unconnected-(MCU1-P5.7{slash}UCA1STE{slash}TB0CLK{slash}S9-Pad90)") (class "Default")
      (node (ref "MCU1") (pin "90") (pinfunction "P5.7/UCA1STE/TB0CLK/S9_90") (pintype "bidirectional"))
    )
    (net (code "108") (name "unconnected-(MCU1-P6.2{slash}COUT{slash}R03-Pad9)") (class "Default")
      (node (ref "MCU1") (pin "9") (pinfunction "P6.2/COUT/R03_9") (pintype "bidirectional"))
    )
    (net (code "109") (name "unconnected-(MCU1-P6.3{slash}COM0-Pad10)") (class "Default")
      (node (ref "MCU1") (pin "10") (pinfunction "P6.3/COM0_10") (pintype "bidirectional"))
    )
    (net (code "110") (name "unconnected-(MCU1-P6.4{slash}TB0.0{slash}COM1-Pad11)") (class "Default")
      (node (ref "MCU1") (pin "11") (pinfunction "P6.4/TB0.0/COM1_11") (pintype "bidirectional"))
    )
    (net (code "111") (name "unconnected-(MCU1-P6.5{slash}TB0.1{slash}COM2-Pad12)") (class "Default")
      (node (ref "MCU1") (pin "12") (pinfunction "P6.5/TB0.1/COM2_12") (pintype "bidirectional"))
    )
    (net (code "112") (name "unconnected-(MCU1-P6.6{slash}TB0.2{slash}COM3-Pad13)") (class "Default")
      (node (ref "MCU1") (pin "13") (pinfunction "P6.6/TB0.2/COM3_13") (pintype "bidirectional"))
    )
    (net (code "113") (name "unconnected-(MCU1-P6.7{slash}TA0CLK{slash}S31-Pad34)") (class "Default")
      (node (ref "MCU1") (pin "34") (pinfunction "P6.7/TA0CLK/S31_34") (pintype "bidirectional"))
    )
    (net (code "114") (name "unconnected-(MCU1-P8.4{slash}A7{slash}C7-Pad59)") (class "Default")
      (node (ref "MCU1") (pin "59") (pinfunction "P8.4/A7/C7_59") (pintype "bidirectional"))
    )
    (net (code "115") (name "unconnected-(MCU1-P8.5{slash}A6{slash}C6-Pad60)") (class "Default")
      (node (ref "MCU1") (pin "60") (pinfunction "P8.5/A6/C6_60") (pintype "bidirectional"))
    )
    (net (code "116") (name "unconnected-(MCU1-P8.6{slash}A5{slash}C5-Pad61)") (class "Default")
      (node (ref "MCU1") (pin "61") (pinfunction "P8.6/A5/C5_61") (pintype "bidirectional"))
    )
    (net (code "117") (name "unconnected-(MCU1-P8.7{slash}A4{slash}C4-Pad62)") (class "Default")
      (node (ref "MCU1") (pin "62") (pinfunction "P8.7/A4/C4_62") (pintype "bidirectional"))
    )
    (net (code "118") (name "unconnected-(MCU1-P9.4{slash}ESICI0{slash}A12{slash}C12-Pad71)") (class "Default")
      (node (ref "MCU1") (pin "71") (pinfunction "P9.4/ESICI0/A12/C12_71") (pintype "bidirectional"))
    )
    (net (code "119") (name "unconnected-(MCU1-P9.5{slash}ESICI1{slash}A13{slash}C13-Pad72)") (class "Default")
      (node (ref "MCU1") (pin "72") (pinfunction "P9.5/ESICI1/A13/C13_72") (pintype "bidirectional"))
    )
    (net (code "120") (name "unconnected-(MCU1-P9.6{slash}ESICI2{slash}A14{slash}C14-Pad73)") (class "Default")
      (node (ref "MCU1") (pin "73") (pinfunction "P9.6/ESICI2/A14/C14_73") (pintype "bidirectional"))
    )
    (net (code "121") (name "unconnected-(MCU1-P10.0{slash}SMCLK{slash}S4-Pad95)") (class "Default")
      (node (ref "MCU1") (pin "95") (pinfunction "P10.0/SMCLK/S4_95") (pintype "bidirectional"))
    )
    (net (code "122") (name "unconnected-(MCU1-P10.1{slash}TA0.0{slash}S28-Pad37)") (class "Default")
      (node (ref "MCU1") (pin "37") (pinfunction "P10.1/TA0.0/S28_37") (pintype "bidirectional"))
    )
    (net (code "123") (name "unconnected-(MCU1-P10.2{slash}TA1.0{slash}SMCLK{slash}S39-Pad18)") (class "Default")
      (node (ref "MCU1") (pin "18") (pinfunction "P10.2/TA1.0/SMCLK/S39_18") (pintype "bidirectional"))
    )
    (net (code "124") (name "unconnected-(MCU1-PJ.4{slash}LFXIN-Pad84)") (class "Default")
      (node (ref "MCU1") (pin "84") (pinfunction "PJ.4/LFXIN_84") (pintype "bidirectional"))
    )
    (net (code "125") (name "unconnected-(MCU1-PJ.5{slash}LFXOUT-Pad85)") (class "Default")
      (node (ref "MCU1") (pin "85") (pinfunction "PJ.5/LFXOUT_85") (pintype "bidirectional"))
    )
    (net (code "126") (name "unconnected-(MCU1-PJ.6{slash}HFXIN-Pad82)") (class "Default")
      (node (ref "MCU1") (pin "82") (pinfunction "PJ.6/HFXIN_82") (pintype "bidirectional"))
    )
    (net (code "127") (name "unconnected-(MCU1-PJ.7{slash}HFXOUT-Pad81)") (class "Default")
      (node (ref "MCU1") (pin "81") (pinfunction "PJ.7/HFXOUT_81") (pintype "bidirectional"))
    )
    (net (code "128") (name "unconnected-(MCU1-P_5.4{slash}UCA1SIMO{slash}UCA1TXD{slash}S12-Pad87)") (class "Default")
      (node (ref "MCU1") (pin "87") (pinfunction "P_5.4/UCA1SIMO/UCA1TXD/S12_87") (pintype "bidirectional"))
    )
    (net (code "129") (name "unconnected-(MCU1-R33{slash}LCDCAP-Pad6)") (class "Default")
      (node (ref "MCU1") (pin "6") (pinfunction "R33/LCDCAP_6") (pintype "bidirectional"))
    )
  )
)
